# MrRoboto.net
KiCad netlist of a schematic drawn in EAGLE
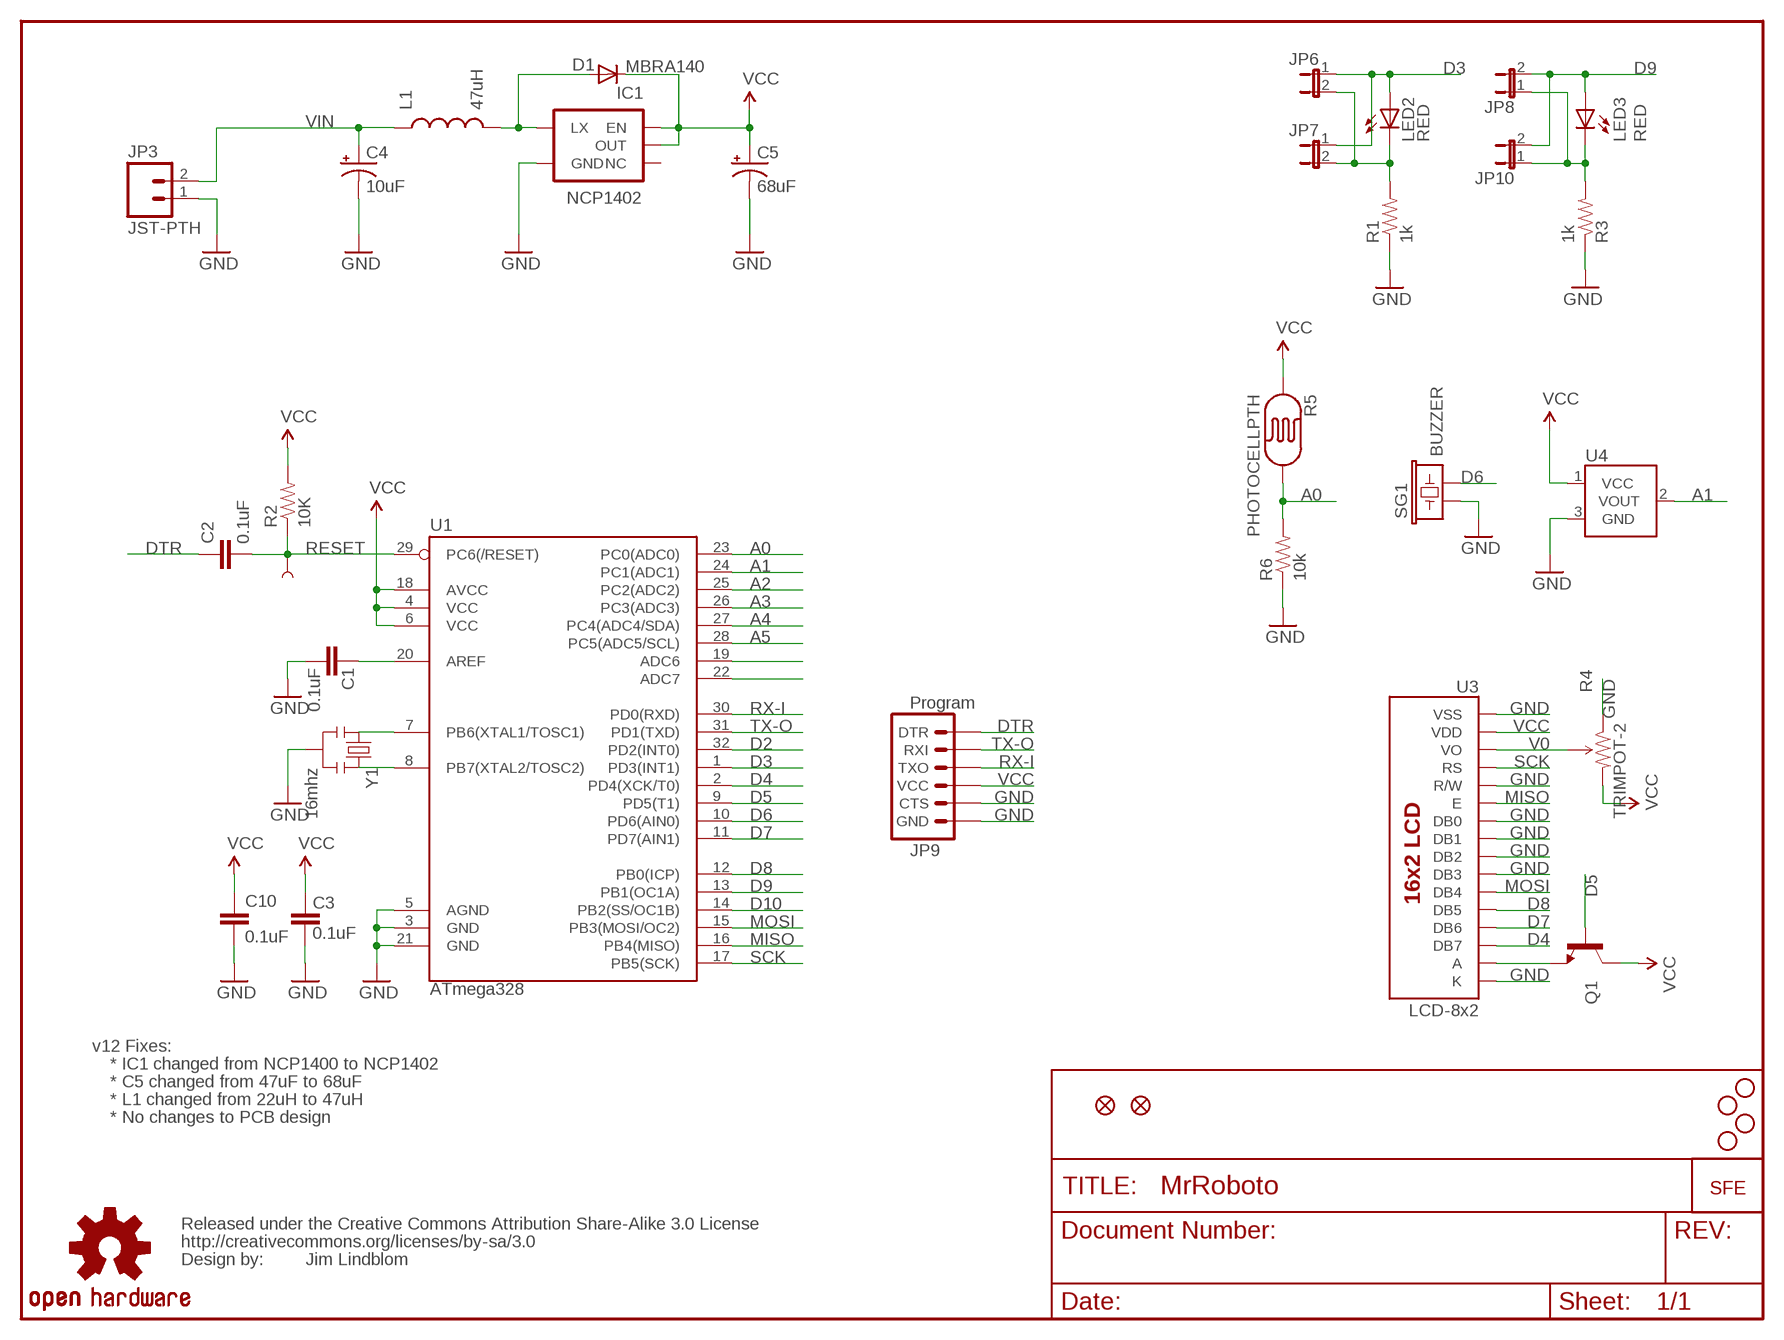
[diagram p0: schematic, sheet 1]

(export (version "E")
  (design (tool "Eeschema 10.0.6"))
  (components
    (comp (ref "C1")
      (value "0.1uF")
      (footprint "eagle-import:0402-CAP")
      (libsource (lib "eagle-import") (part "CAP0402-CAP"))
    )
    (comp (ref "C2")
      (value "0.1uF")
      (footprint "eagle-import:0402-CAP")
      (libsource (lib "eagle-import") (part "CAP0402-CAP"))
    )
    (comp (ref "C3")
      (value "0.1uF")
      (footprint "eagle-import:0402-CAP")
      (libsource (lib "eagle-import") (part "CAP0402-CAP"))
    )
    (comp (ref "C4")
      (value "10uF")
      (footprint "eagle-import:EIA3216")
      (libsource (lib "eagle-import") (part "CAP_POL1206"))
    )
    (comp (ref "C5")
      (value "68uF")
      (footprint "eagle-import:EIA3528")
      (libsource (lib "eagle-import") (part "CAP_POL3528"))
    )
    (comp (ref "C10")
      (value "0.1uF")
      (footprint "eagle-import:0402-CAP")
      (libsource (lib "eagle-import") (part "CAP0402-CAP"))
    )
    (comp (ref "D1")
      (value "MBRA140")
      (footprint "eagle-import:SMA-DIODE")
      (libsource (lib "eagle-import") (part "DIODESMA"))
    )
    (comp (ref "IC1")
      (value "NCP1402")
      (footprint "eagle-import:SOT23-5")
      (libsource (lib "eagle-import") (part "V_REG_NCP1400SOT23-5"))
    )
    (comp (ref "JP1")
      (value "Long, Plastic")
      (footprint "eagle-import:STAND-OFF")
      (libsource (lib "eagle-import") (part "STAND-OFF"))
    )
    (comp (ref "JP2")
      (value "Long, Plastic")
      (footprint "eagle-import:STAND-OFF")
      (libsource (lib "eagle-import") (part "STAND-OFF"))
    )
    (comp (ref "JP3")
      (value "JST-PTH")
      (footprint "eagle-import:JST-2-PTH-KIT")
      (libsource (lib "eagle-import") (part "M02JST-PTH-2-KIT"))
    )
    (comp (ref "JP4")
      (value "Long, Plastic")
      (footprint "eagle-import:STAND-OFF")
      (libsource (lib "eagle-import") (part "STAND-OFF"))
    )
    (comp (ref "JP5")
      (value "Long, Plastic")
      (footprint "eagle-import:STAND-OFF")
      (libsource (lib "eagle-import") (part "STAND-OFF"))
    )
    (comp (ref "JP6")
      (value "JUMPER-2SMD-NO-NS")
      (footprint "eagle-import:SJ_2S-NO-NS")
      (libsource (lib "eagle-import") (part "JUMPER-2SMD-NO-NS"))
    )
    (comp (ref "JP7")
      (value "JUMPER-2SMD-NO-NS")
      (footprint "eagle-import:SJ_2S-NO-NS")
      (libsource (lib "eagle-import") (part "JUMPER-2SMD-NO-NS"))
    )
    (comp (ref "JP8")
      (value "JUMPER-2SMD-NO-NS")
      (footprint "eagle-import:SJ_2S-NO-NS")
      (libsource (lib "eagle-import") (part "JUMPER-2SMD-NO-NS"))
    )
    (comp (ref "JP9")
      (value "Program")
      (footprint "eagle-import:1X06-KIT")
      (libsource (lib "eagle-import") (part "ARDUINO_SERIAL_PROGRAMPTH-KIT"))
    )
    (comp (ref "JP10")
      (value "JUMPER-2SMD-NO-NS")
      (footprint "eagle-import:SJ_2S-NO-NS")
      (libsource (lib "eagle-import") (part "JUMPER-2SMD-NO-NS"))
    )
    (comp (ref "JP11")
      (value "FIDUCIAL1X2.5")
      (footprint "eagle-import:FIDUCIAL-1X2.5")
      (libsource (lib "eagle-import") (part "FIDUCIAL1X2.5"))
    )
    (comp (ref "JP12")
      (value "FIDUCIAL1X2.5")
      (footprint "eagle-import:FIDUCIAL-1X2.5")
      (libsource (lib "eagle-import") (part "FIDUCIAL1X2.5"))
    )
    (comp (ref "L1")
      (value "47uH")
      (footprint "eagle-import:CR54")
      (libsource (lib "eagle-import") (part "INDUCTORCR54"))
    )
    (comp (ref "LED2")
      (value "RED")
      (footprint "eagle-import:LED5MM-KIT")
      (libsource (lib "eagle-import") (part "LED5MM-KIT"))
    )
    (comp (ref "LED3")
      (value "RED")
      (footprint "eagle-import:LED5MM-KIT")
      (libsource (lib "eagle-import") (part "LED5MM-KIT"))
    )
    (comp (ref "Q1")
      (value "TRANSISTOR_NPNSOT23")
      (footprint "eagle-import:SOT23")
      (libsource (lib "eagle-import") (part "TRANSISTOR_NPNSOT23"))
    )
    (comp (ref "R1")
      (value "1k")
      (footprint "eagle-import:AXIAL-0.3-KIT")
      (libsource (lib "eagle-import") (part "RESISTORKIT"))
    )
    (comp (ref "R2")
      (value "10K")
      (footprint "eagle-import:0402-RES")
      (libsource (lib "eagle-import") (part "RESISTOR0402-RES"))
    )
    (comp (ref "R3")
      (value "1k")
      (footprint "eagle-import:AXIAL-0.3-KIT")
      (libsource (lib "eagle-import") (part "RESISTORKIT"))
    )
    (comp (ref "R4")
      (value "TRIMPOT-2")
      (footprint "eagle-import:TRIMPOT_TC33")
      (libsource (lib "eagle-import") (part "TRIMPOT-2"))
    )
    (comp (ref "R5")
      (value "PHOTOCELLPTH")
      (footprint "eagle-import:PHOTOCELL-KIT")
      (libsource (lib "eagle-import") (part "PHOTOCELLPTH-KIT"))
    )
    (comp (ref "R6")
      (value "10k")
      (footprint "eagle-import:0402-RES")
      (libsource (lib "eagle-import") (part "RESISTOR0402-RES"))
    )
    (comp (ref "SG1")
      (value "BUZZER")
      (footprint "eagle-import:BUZZER-12MM-NS-KIT")
      (libsource (lib "eagle-import") (part "BUZZERPTH-NS-KIT"))
    )
    (comp (ref "TP1")
      (value "TP")
      (footprint "eagle-import:PAD.03X.05")
      (libsource (lib "eagle-import") (part "TEST-POINT3X5"))
    )
    (comp (ref "U$1")
      (value "CREATIVE_COMMONS")
      (footprint "eagle-import:CREATIVE_COMMONS")
      (libsource (lib "eagle-import") (part "CREATIVE_COMMONS"))
    )
    (comp (ref "U$2")
      (value "OSHW-LOGOM")
      (footprint "eagle-import:OSHW-LOGO-M")
      (libsource (lib "eagle-import") (part "OSHW-LOGOM"))
    )
    (comp (ref "U$3")
      (value "LOGO-SFENEW")
      (footprint "eagle-import:SFE-NEW-WEBLOGO")
      (libsource (lib "eagle-import") (part "LOGO-SFENEW"))
    )
    (comp (ref "U1")
      (value "ATmega328")
      (footprint "eagle-import:TQFP32-08")
      (libsource (lib "eagle-import") (part "ATMEGA168"))
    )
    (comp (ref "U3")
      (value "LCD-8x2")
      (footprint "eagle-import:LCD-8X2-KIT")
      (libsource (lib "eagle-import") (part "LCD-16X28X2-KIT"))
    )
    (comp (ref "U4")
      (value "TMP36TO-92-KIT")
      (footprint "eagle-import:TO-92-KIT")
      (libsource (lib "eagle-import") (part "TMP36TO-92-KIT"))
    )
    (comp (ref "Y1")
      (value "16mhz")
      (footprint "eagle-import:RESONATOR-SMD")
      (libsource (lib "eagle-import") (part "RESONATORSMD"))
    )
  )
  (nets
    (net (code "1") (name "/A0") (class "Default")
      (node (ref "R5") (pin "2") (pinfunction "P$2_2") (pintype "bidirectional"))
      (node (ref "R6") (pin "2") (pinfunction "2_2") (pintype "passive"))
      (node (ref "U1") (pin "23") (pinfunction "PC0(ADC0)_23") (pintype "bidirectional"))
    )
    (net (code "2") (name "/A1") (class "Default")
      (node (ref "U1") (pin "24") (pinfunction "PC1(ADC1)_24") (pintype "bidirectional"))
      (node (ref "U4") (pin "2") (pinfunction "VOUT_2") (pintype "bidirectional"))
    )
    (net (code "3") (name "/A2") (class "Default")
      (node (ref "U1") (pin "25") (pinfunction "PC2(ADC2)_25") (pintype "bidirectional"))
    )
    (net (code "4") (name "/A3") (class "Default")
      (node (ref "U1") (pin "26") (pinfunction "PC3(ADC3)_26") (pintype "bidirectional"))
    )
    (net (code "5") (name "/A4") (class "Default")
      (node (ref "U1") (pin "27") (pinfunction "PC4(ADC4/SDA)_27") (pintype "bidirectional"))
    )
    (net (code "6") (name "/A5") (class "Default")
      (node (ref "U1") (pin "28") (pinfunction "PC5(ADC5/SCL)_28") (pintype "bidirectional"))
    )
    (net (code "7") (name "/D2") (class "Default")
      (node (ref "U1") (pin "32") (pinfunction "PD2(INT0)_32") (pintype "bidirectional"))
    )
    (net (code "8") (name "/D3") (class "Default")
      (node (ref "JP6") (pin "1") (pinfunction "1_1") (pintype "passive"))
      (node (ref "JP7") (pin "1") (pinfunction "1_1") (pintype "passive"))
      (node (ref "LED2") (pin "A") (pinfunction "A_A") (pintype "passive"))
      (node (ref "U1") (pin "1") (pinfunction "PD3(INT1)_1") (pintype "bidirectional"))
    )
    (net (code "9") (name "/D4") (class "Default")
      (node (ref "U1") (pin "2") (pinfunction "PD4(XCK/T0)_2") (pintype "bidirectional"))
      (node (ref "U3") (pin "14") (pinfunction "DB7_14") (pintype "bidirectional"))
    )
    (net (code "10") (name "/D5") (class "Default")
      (node (ref "Q1") (pin "1") (pinfunction "B_1") (pintype "passive"))
      (node (ref "U1") (pin "9") (pinfunction "PD5(T1)_9") (pintype "bidirectional"))
    )
    (net (code "11") (name "/D6") (class "Default")
      (node (ref "SG1") (pin "-") (pinfunction "2_-") (pintype "passive"))
      (node (ref "U1") (pin "10") (pinfunction "PD6(AIN0)_10") (pintype "bidirectional"))
    )
    (net (code "12") (name "/D7") (class "Default")
      (node (ref "U1") (pin "11") (pinfunction "PD7(AIN1)_11") (pintype "bidirectional"))
      (node (ref "U3") (pin "13") (pinfunction "DB6_13") (pintype "bidirectional"))
    )
    (net (code "13") (name "/D8") (class "Default")
      (node (ref "U1") (pin "12") (pinfunction "PB0(ICP)_12") (pintype "bidirectional"))
      (node (ref "U3") (pin "12") (pinfunction "DB5_12") (pintype "bidirectional"))
    )
    (net (code "14") (name "/D9") (class "Default")
      (node (ref "JP10") (pin "2") (pinfunction "2_2") (pintype "passive"))
      (node (ref "JP8") (pin "2") (pinfunction "2_2") (pintype "passive"))
      (node (ref "LED3") (pin "A") (pinfunction "A_A") (pintype "passive"))
      (node (ref "U1") (pin "13") (pinfunction "PB1(OC1A)_13") (pintype "bidirectional"))
    )
    (net (code "15") (name "/D10") (class "Default")
      (node (ref "U1") (pin "14") (pinfunction "PB2(SS/OC1B)_14") (pintype "bidirectional"))
    )
    (net (code "16") (name "/DTR") (class "Default")
      (node (ref "C2") (pin "1") (pinfunction "1_1") (pintype "passive"))
      (node (ref "JP9") (pin "1") (pinfunction "DTR_1") (pintype "passive"))
    )
    (net (code "17") (name "/MISO") (class "Default")
      (node (ref "U1") (pin "16") (pinfunction "PB4(MISO)_16") (pintype "bidirectional"))
      (node (ref "U3") (pin "6") (pinfunction "E_6") (pintype "input"))
    )
    (net (code "18") (name "/MOSI") (class "Default")
      (node (ref "U1") (pin "15") (pinfunction "PB3(MOSI/OC2)_15") (pintype "bidirectional"))
      (node (ref "U3") (pin "11") (pinfunction "DB4_11") (pintype "bidirectional"))
    )
    (net (code "19") (name "/RESET") (class "Default")
      (node (ref "C2") (pin "2") (pinfunction "2_2") (pintype "passive"))
      (node (ref "R2") (pin "1") (pinfunction "1_1") (pintype "passive"))
      (node (ref "TP1") (pin "P$1") (pinfunction "1_P$1") (pintype "bidirectional"))
      (node (ref "U1") (pin "29") (pinfunction "PC6(/RESET)_29") (pintype "bidirectional"))
    )
    (net (code "20") (name "/RX-I") (class "Default")
      (node (ref "JP9") (pin "3") (pinfunction "TXO_3") (pintype "passive"))
      (node (ref "U1") (pin "30") (pinfunction "PD0(RXD)_30") (pintype "bidirectional"))
    )
    (net (code "21") (name "/SCK") (class "Default")
      (node (ref "U1") (pin "17") (pinfunction "PB5(SCK)_17") (pintype "bidirectional"))
      (node (ref "U3") (pin "4") (pinfunction "RS_4") (pintype "input"))
    )
    (net (code "22") (name "/TX-O") (class "Default")
      (node (ref "JP9") (pin "2") (pinfunction "RXI_2") (pintype "passive"))
      (node (ref "U1") (pin "31") (pinfunction "PD1(TXD)_31") (pintype "bidirectional"))
    )
    (net (code "23") (name "/V0") (class "Default")
      (node (ref "R4") (pin "2") (pinfunction "WIPER_2") (pintype "passive"))
      (node (ref "U3") (pin "3") (pinfunction "VO_3") (pintype "bidirectional"))
    )
    (net (code "24") (name "/VIN") (class "Default")
      (node (ref "C4") (pin "A") (pinfunction "+_A") (pintype "passive"))
      (node (ref "JP3") (pin "2") (pinfunction "2_2") (pintype "passive"))
      (node (ref "L1") (pin "P$1") (pinfunction "1_P$1") (pintype "passive"))
    )
    (net (code "25") (name "GND") (class "Default")
      (node (ref "C1") (pin "1") (pinfunction "1_1") (pintype "passive"))
      (node (ref "C10") (pin "2") (pinfunction "2_2") (pintype "passive"))
      (node (ref "C3") (pin "1") (pinfunction "1_1") (pintype "passive"))
      (node (ref "C4") (pin "C") (pinfunction "-_C") (pintype "passive"))
      (node (ref "C5") (pin "C") (pinfunction "-_C") (pintype "passive"))
      (node (ref "IC1") (pin "4") (pinfunction "GND_4") (pintype "input"))
      (node (ref "JP3") (pin "1") (pinfunction "1_1") (pintype "passive"))
      (node (ref "JP9") (pin "5") (pinfunction "CTS_5") (pintype "passive"))
      (node (ref "JP9") (pin "6") (pinfunction "GND_6") (pintype "passive"))
      (node (ref "R1") (pin "P$1") (pinfunction "1_P$1") (pintype "passive"))
      (node (ref "R3") (pin "P$1") (pinfunction "1_P$1") (pintype "passive"))
      (node (ref "R4") (pin "1") (pinfunction "CCW_1") (pintype "passive"))
      (node (ref "R6") (pin "1") (pinfunction "1_1") (pintype "passive"))
      (node (ref "SG1") (pin "+") (pinfunction "1_+") (pintype "passive"))
      (node (ref "U1") (pin "21") (pinfunction "GND_21") (pintype "bidirectional"))
      (node (ref "U1") (pin "3") (pinfunction "GND_3") (pintype "bidirectional"))
      (node (ref "U1") (pin "5") (pinfunction "AGND_5") (pintype "bidirectional"))
      (node (ref "U3") (pin "1") (pinfunction "VSS_1") (pintype "power_in"))
      (node (ref "U3") (pin "10") (pinfunction "DB3_10") (pintype "bidirectional"))
      (node (ref "U3") (pin "16") (pinfunction "K_16") (pintype "power_in"))
      (node (ref "U3") (pin "5") (pinfunction "R/W_5") (pintype "input"))
      (node (ref "U3") (pin "7") (pinfunction "DB0_7") (pintype "bidirectional"))
      (node (ref "U3") (pin "8") (pinfunction "DB1_8") (pintype "bidirectional"))
      (node (ref "U3") (pin "9") (pinfunction "DB2_9") (pintype "bidirectional"))
      (node (ref "U4") (pin "3") (pinfunction "GND_3") (pintype "bidirectional"))
      (node (ref "Y1") (pin "2") (pinfunction "2_2") (pintype "passive"))
    )
    (net (code "26") (name "Net-(IC1-LX)") (class "Default")
      (node (ref "D1") (pin "A") (pinfunction "A_A") (pintype "passive"))
      (node (ref "IC1") (pin "5") (pinfunction "LX_5") (pintype "input"))
      (node (ref "L1") (pin "P$2") (pinfunction "2_P$2") (pintype "passive"))
    )
    (net (code "27") (name "Net-(LED2-C)") (class "Default")
      (node (ref "JP6") (pin "2") (pinfunction "2_2") (pintype "passive"))
      (node (ref "JP7") (pin "2") (pinfunction "2_2") (pintype "passive"))
      (node (ref "LED2") (pin "K") (pinfunction "C_K") (pintype "passive"))
      (node (ref "R1") (pin "P$2") (pinfunction "2_P$2") (pintype "passive"))
    )
    (net (code "28") (name "Net-(LED3-C)") (class "Default")
      (node (ref "JP10") (pin "1") (pinfunction "1_1") (pintype "passive"))
      (node (ref "JP8") (pin "1") (pinfunction "1_1") (pintype "passive"))
      (node (ref "LED3") (pin "K") (pinfunction "C_K") (pintype "passive"))
      (node (ref "R3") (pin "P$2") (pinfunction "2_P$2") (pintype "passive"))
    )
    (net (code "29") (name "Net-(Q1-E)") (class "Default")
      (node (ref "Q1") (pin "2") (pinfunction "E_2") (pintype "passive"))
      (node (ref "U3") (pin "15") (pinfunction "A_15") (pintype "power_in"))
    )
    (net (code "30") (name "Net-(U1-AREF)") (class "Default")
      (node (ref "C1") (pin "2") (pinfunction "2_2") (pintype "passive"))
      (node (ref "U1") (pin "20") (pinfunction "AREF_20") (pintype "bidirectional"))
    )
    (net (code "31") (name "Net-(U1-PB6(XTAL1{slash}TOSC1))") (class "Default")
      (node (ref "U1") (pin "7") (pinfunction "PB6(XTAL1/TOSC1)_7") (pintype "bidirectional"))
      (node (ref "Y1") (pin "1") (pinfunction "1_1") (pintype "passive"))
    )
    (net (code "32") (name "Net-(U1-PB7(XTAL2{slash}TOSC2))") (class "Default")
      (node (ref "U1") (pin "8") (pinfunction "PB7(XTAL2/TOSC2)_8") (pintype "bidirectional"))
      (node (ref "Y1") (pin "3") (pinfunction "3_3") (pintype "passive"))
    )
    (net (code "33") (name "VCC") (class "Default")
      (node (ref "C10") (pin "1") (pinfunction "1_1") (pintype "passive"))
      (node (ref "C3") (pin "2") (pinfunction "2_2") (pintype "passive"))
      (node (ref "C5") (pin "A") (pinfunction "+_A") (pintype "passive"))
      (node (ref "D1") (pin "C") (pinfunction "C_C") (pintype "passive"))
      (node (ref "IC1") (pin "1") (pinfunction "EN_1") (pintype "input"))
      (node (ref "IC1") (pin "2") (pinfunction "OUT_2") (pintype "passive"))
      (node (ref "JP9") (pin "4") (pinfunction "VCC_4") (pintype "passive"))
      (node (ref "Q1") (pin "3") (pinfunction "C_3") (pintype "passive"))
      (node (ref "R2") (pin "2") (pinfunction "2_2") (pintype "passive"))
      (node (ref "R4") (pin "3") (pinfunction "CW_3") (pintype "passive"))
      (node (ref "R5") (pin "1") (pinfunction "P$1_1") (pintype "bidirectional"))
      (node (ref "U1") (pin "18") (pinfunction "AVCC_18") (pintype "bidirectional"))
      (node (ref "U1") (pin "4") (pinfunction "VCC_4") (pintype "bidirectional"))
      (node (ref "U1") (pin "6") (pinfunction "VCC_6") (pintype "bidirectional"))
      (node (ref "U3") (pin "2") (pinfunction "VDD_2") (pintype "power_in"))
      (node (ref "U4") (pin "1") (pinfunction "VCC_1") (pintype "bidirectional"))
    )
    (net (code "34") (name "unconnected-(IC1-NC-Pad3)") (class "Default")
      (node (ref "IC1") (pin "3") (pinfunction "NC_3") (pintype "input"))
    )
    (net (code "35") (name "unconnected-(U1-ADC6-Pad19)") (class "Default")
      (node (ref "U1") (pin "19") (pinfunction "ADC6_19") (pintype "bidirectional"))
    )
    (net (code "36") (name "unconnected-(U1-ADC7-Pad22)") (class "Default")
      (node (ref "U1") (pin "22") (pinfunction "ADC7_22") (pintype "bidirectional"))
    )
  )
)
